# BOTTOM_BRD_v1_0_1.net
KiCad netlist of a schematic drawn in EAGLE
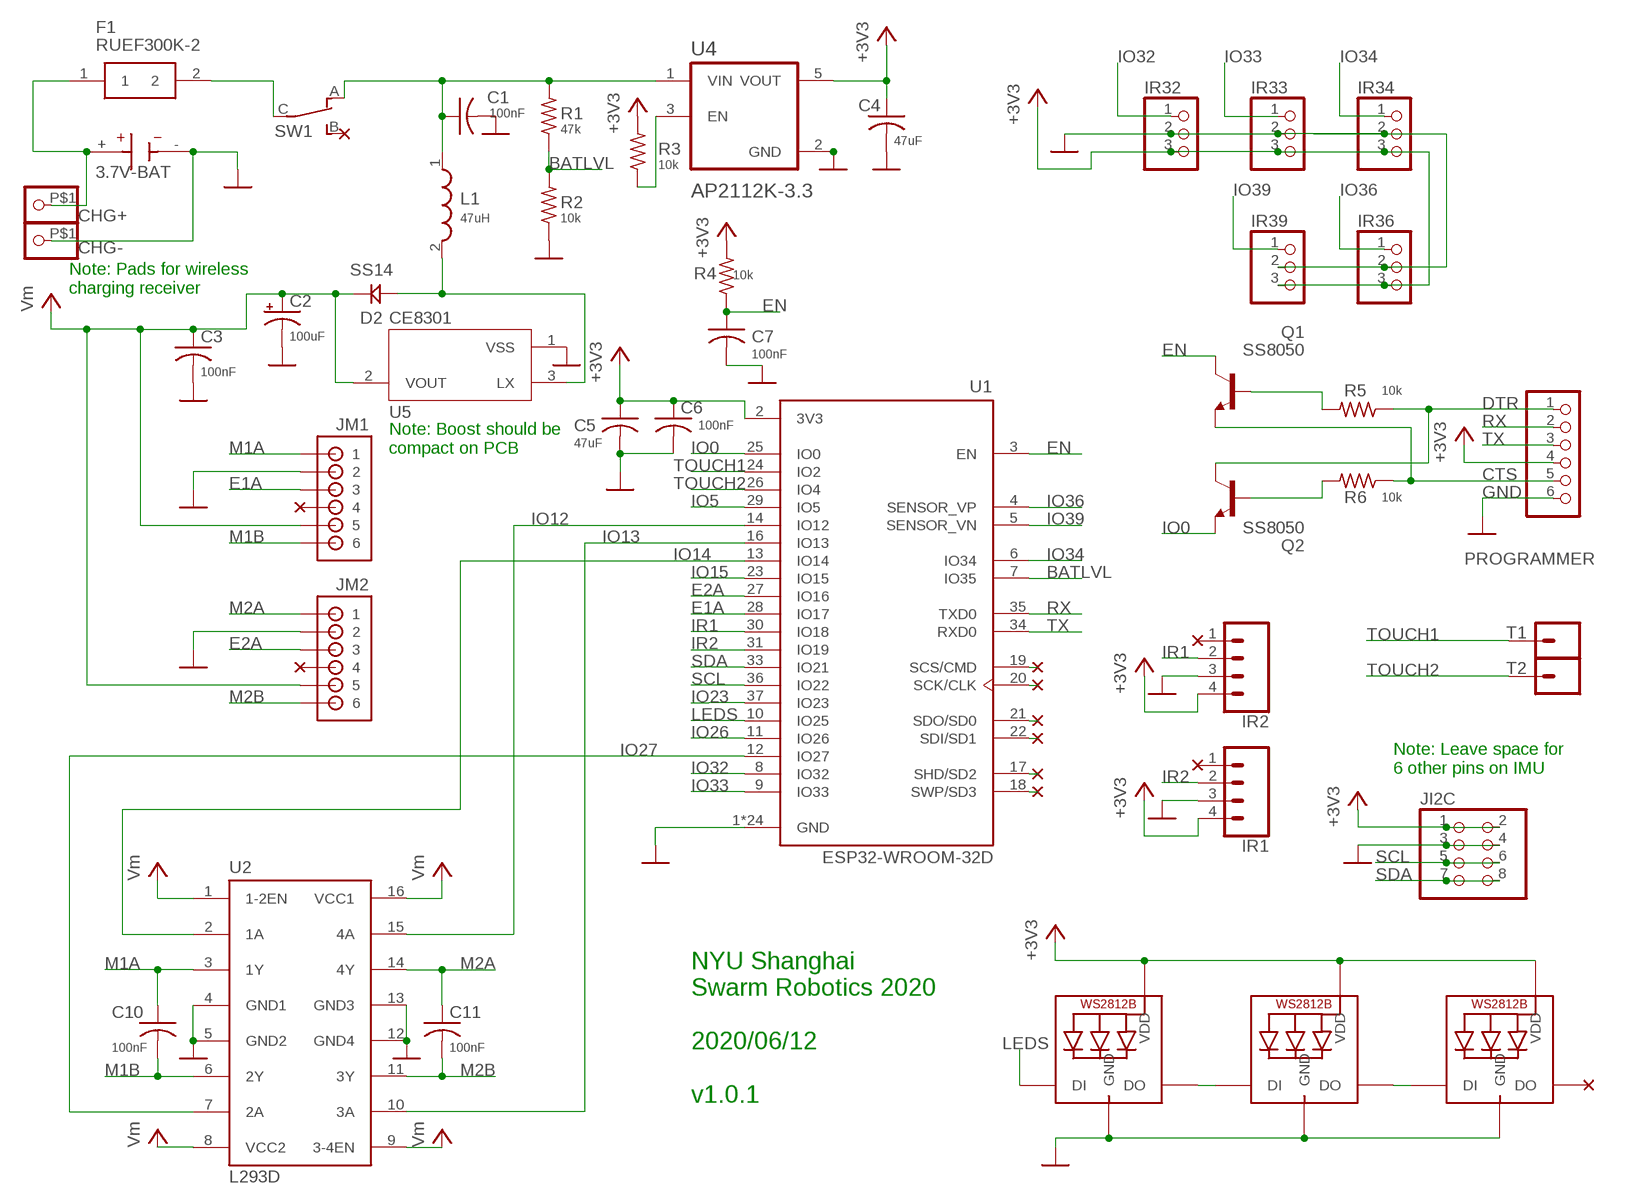
[diagram p0: schematic, sheet 1]

(export (version "E")
  (design (tool "Eeschema 10.0.6"))
  (components
    (comp (ref "BT1")
      (value "3.7V-BAT")
      (footprint "eagle-import:BAT_6S-AA")
      (fields (field (name "MF") "MPD") (field (name "MP") "6S-AA"))
      (libsource (lib "eagle-import") (part "6S-AA"))
    )
    (comp (ref "C1")
      (value "100nF")
      (footprint "eagle-import:C0805")
      (libsource (lib "eagle-import") (part "C-USC0805"))
    )
    (comp (ref "C2")
      (value "100uF")
      (footprint "eagle-import:153CLV-0605")
      (libsource (lib "eagle-import") (part "CPOL-US153CLV-0605"))
    )
    (comp (ref "C3")
      (value "100nF")
      (footprint "eagle-import:C0805")
      (libsource (lib "eagle-import") (part "C-USC0805"))
    )
    (comp (ref "C4")
      (value "47uF")
      (footprint "eagle-import:C0805")
      (libsource (lib "eagle-import") (part "C-USC0805"))
    )
    (comp (ref "C5")
      (value "47uF")
      (footprint "eagle-import:C0805")
      (libsource (lib "eagle-import") (part "C-USC0805"))
    )
    (comp (ref "C6")
      (value "100nF")
      (footprint "eagle-import:C0805")
      (libsource (lib "eagle-import") (part "C-USC0805"))
    )
    (comp (ref "C7")
      (value "100nF")
      (footprint "eagle-import:C0805")
      (libsource (lib "eagle-import") (part "C-USC0805"))
    )
    (comp (ref "C10")
      (value "100nF")
      (footprint "eagle-import:C0805")
      (libsource (lib "eagle-import") (part "C-USC0805"))
    )
    (comp (ref "C11")
      (value "100nF")
      (footprint "eagle-import:C0805")
      (libsource (lib "eagle-import") (part "C-USC0805"))
    )
    (comp (ref "CHARGING")
      (value "WS2812B5050")
      (footprint "eagle-import:WS2812B")
      (libsource (lib "eagle-import") (part "WS2812B5050"))
    )
    (comp (ref "CHG+")
      (value "PINHD-1X1-BIGPOGO")
      (footprint "eagle-import:1X1-BIGPOGO")
      (libsource (lib "eagle-import") (part "PINHD-1X1-BIGPOGO"))
    )
    (comp (ref "CHG-")
      (value "PINHD-1X1-BIGPOGO")
      (footprint "eagle-import:1X1-BIGPOGO")
      (libsource (lib "eagle-import") (part "PINHD-1X1-BIGPOGO"))
    )
    (comp (ref "D2")
      (value "SS14")
      (footprint "eagle-import:DO214")
      (fields (field (name "MF") "ON Semiconductor"))
      (libsource (lib "eagle-import") (part "SS14"))
    )
    (comp (ref "F1")
      (value "RUEF300K-2")
      (footprint "eagle-import:RUEF300K2")
      (libsource (lib "eagle-import") (part "RUEF300K-2"))
    )
    (comp (ref "IR1")
      (value "CONN_04")
      (footprint "eagle-import:1X04")
      (libsource (lib "eagle-import") (part "CONN_04"))
    )
    (comp (ref "IR2")
      (value "CONN_04")
      (footprint "eagle-import:1X04")
      (libsource (lib "eagle-import") (part "CONN_04"))
    )
    (comp (ref "IR32")
      (value "PINHD-1X3")
      (footprint "eagle-import:1X03")
      (libsource (lib "eagle-import") (part "PINHD-1X3"))
    )
    (comp (ref "IR33")
      (value "PINHD-1X3")
      (footprint "eagle-import:1X03")
      (libsource (lib "eagle-import") (part "PINHD-1X3"))
    )
    (comp (ref "IR34")
      (value "PINHD-1X3")
      (footprint "eagle-import:1X03")
      (libsource (lib "eagle-import") (part "PINHD-1X3"))
    )
    (comp (ref "IR36")
      (value "PINHD-1X3")
      (footprint "eagle-import:1X03")
      (libsource (lib "eagle-import") (part "PINHD-1X3"))
    )
    (comp (ref "IR39")
      (value "PINHD-1X3")
      (footprint "eagle-import:1X03")
      (libsource (lib "eagle-import") (part "PINHD-1X3"))
    )
    (comp (ref "JI2C")
      (value "PINHD-2X4")
      (footprint "eagle-import:2X04")
      (libsource (lib "eagle-import") (part "PINHD-2X4"))
    )
    (comp (ref "JM1")
      (value "B6B-ZR")
      (footprint "eagle-import:B6B-ZR")
      (fields (field (name "MF") "JST"))
      (libsource (lib "eagle-import") (part "B6B-ZR"))
    )
    (comp (ref "JM2")
      (value "B6B-ZR")
      (footprint "eagle-import:B6B-ZR")
      (fields (field (name "MF") "JST"))
      (libsource (lib "eagle-import") (part "B6B-ZR"))
    )
    (comp (ref "L1")
      (value "47uH")
      (footprint "eagle-import:INDP5858X480N")
      (fields (field (name "MF") "Bourns") (field (name "MP") "SDR0604-100KL"))
      (libsource (lib "eagle-import") (part "SDR0604-100KL"))
    )
    (comp (ref "POWER")
      (value "WS2812B5050")
      (footprint "eagle-import:WS2812B")
      (libsource (lib "eagle-import") (part "WS2812B5050"))
    )
    (comp (ref "PROGRAMMER")
      (value "PINHD-1X6B")
      (footprint "eagle-import:1X06-BIG")
      (libsource (lib "eagle-import") (part "PINHD-1X6B"))
    )
    (comp (ref "Q1")
      (value "SS8050")
      (footprint "eagle-import:SOT23")
      (libsource (lib "eagle-import") (part "BC850"))
    )
    (comp (ref "Q2")
      (value "SS8050")
      (footprint "eagle-import:SOT23")
      (libsource (lib "eagle-import") (part "BC850"))
    )
    (comp (ref "R1")
      (value "47k")
      (footprint "eagle-import:M0805")
      (libsource (lib "eagle-import") (part "R-US_M0805"))
    )
    (comp (ref "R2")
      (value "10k")
      (footprint "eagle-import:M0805")
      (libsource (lib "eagle-import") (part "R-US_M0805"))
    )
    (comp (ref "R3")
      (value "10k")
      (footprint "eagle-import:M0805")
      (libsource (lib "eagle-import") (part "R-US_M0805"))
    )
    (comp (ref "R4")
      (value "10k")
      (footprint "eagle-import:M0805")
      (libsource (lib "eagle-import") (part "R-US_M0805"))
    )
    (comp (ref "R5")
      (value "10k")
      (footprint "eagle-import:M0805")
      (libsource (lib "eagle-import") (part "R-US_M0805"))
    )
    (comp (ref "R6")
      (value "10k")
      (footprint "eagle-import:M0805")
      (libsource (lib "eagle-import") (part "R-US_M0805"))
    )
    (comp (ref "STATE")
      (value "WS2812B5050")
      (footprint "eagle-import:WS2812B")
      (libsource (lib "eagle-import") (part "WS2812B5050"))
    )
    (comp (ref "SW1")
      (value "CS12ANW03")
      (footprint "eagle-import:CS12ANW03")
      (fields (field (name "MF") "NKK Switches"))
      (libsource (lib "eagle-import") (part "CS12ANW03"))
    )
    (comp (ref "T1")
      (value "CONN_01SPRING-CONN")
      (footprint "eagle-import:SPRING-CONNECTOR")
      (libsource (lib "eagle-import") (part "CONN_01SPRING-CONN"))
    )
    (comp (ref "T2")
      (value "CONN_01SPRING-CONN")
      (footprint "eagle-import:SPRING-CONNECTOR")
      (libsource (lib "eagle-import") (part "CONN_01SPRING-CONN"))
    )
    (comp (ref "U1")
      (value "ESP32-WROOM-32D")
      (footprint "eagle-import:MODULE_ESP32-WROOM-32D")
      (fields (field (name "MF") "Espressif Systems"))
      (libsource (lib "eagle-import") (part "ESP32-WROOM-32D"))
    )
    (comp (ref "U2")
      (value "L293D")
      (footprint "eagle-import:DIL16")
      (libsource (lib "eagle-import") (part "L293D"))
    )
    (comp (ref "U4")
      (value "AP2112K-3.3")
      (footprint "eagle-import:SOT95P285X140-5N")
      (fields (field (name "MF") "Diodes Inc.") (field (name "MP") "AP2112K-3.3TRG1"))
      (libsource (lib "eagle-import") (part "AP2112K-3.3TRG1"))
    )
    (comp (ref "U5")
      (value "CE8301")
      (footprint "eagle-import:REG_MCP1702T-3302E_MB")
      (fields (field (name "MF") "Microchip") (field (name "MP") "MCP1702T-3302E/MB"))
      (libsource (lib "eagle-import") (part "MCP1702T-3302E/MB"))
    )
  )
  (nets
    (net (code "1") (name "+3V3") (class "Default")
      (node (ref "C4") (pin "1") (pinfunction "1_1") (pintype "passive"))
      (node (ref "C5") (pin "1") (pinfunction "1_1") (pintype "passive"))
      (node (ref "C6") (pin "1") (pinfunction "1_1") (pintype "passive"))
      (node (ref "CHARGING") (pin "1-VDD") (pinfunction "VDD_1-VDD") (pintype "power_in"))
      (node (ref "IR1") (pin "4") (pinfunction "4_4") (pintype "passive"))
      (node (ref "IR2") (pin "4") (pinfunction "4_4") (pintype "passive"))
      (node (ref "IR32") (pin "3") (pinfunction "3_3") (pintype "passive"))
      (node (ref "IR33") (pin "3") (pinfunction "3_3") (pintype "passive"))
      (node (ref "IR34") (pin "3") (pinfunction "3_3") (pintype "passive"))
      (node (ref "IR36") (pin "3") (pinfunction "3_3") (pintype "passive"))
      (node (ref "IR39") (pin "3") (pinfunction "3_3") (pintype "passive"))
      (node (ref "JI2C") (pin "1") (pinfunction "1_1") (pintype "passive"))
      (node (ref "JI2C") (pin "2") (pinfunction "2_2") (pintype "passive"))
      (node (ref "POWER") (pin "1-VDD") (pinfunction "VDD_1-VDD") (pintype "power_in"))
      (node (ref "PROGRAMMER") (pin "4") (pinfunction "4_4") (pintype "passive"))
      (node (ref "R3") (pin "2") (pinfunction "2_2") (pintype "passive"))
      (node (ref "R4") (pin "2") (pinfunction "2_2") (pintype "passive"))
      (node (ref "STATE") (pin "1-VDD") (pinfunction "VDD_1-VDD") (pintype "power_in"))
      (node (ref "U1") (pin "2") (pinfunction "3V3_2") (pintype "power_in"))
      (node (ref "U4") (pin "5") (pinfunction "VOUT_5") (pintype "power_in"))
    )
    (net (code "2") (name "/BATLVL") (class "Default")
      (node (ref "R1") (pin "1") (pinfunction "1_1") (pintype "passive"))
      (node (ref "R2") (pin "2") (pinfunction "2_2") (pintype "passive"))
      (node (ref "U1") (pin "7") (pinfunction "IO35_7") (pintype "input"))
    )
    (net (code "3") (name "/CTS") (class "Default")
      (node (ref "PROGRAMMER") (pin "5") (pinfunction "5_5") (pintype "passive"))
      (node (ref "Q1") (pin "2") (pinfunction "E_2") (pintype "passive"))
      (node (ref "R6") (pin "1") (pinfunction "1_1") (pintype "passive"))
    )
    (net (code "4") (name "/DTR") (class "Default")
      (node (ref "PROGRAMMER") (pin "1") (pinfunction "1_1") (pintype "passive"))
      (node (ref "Q2") (pin "3") (pinfunction "C_3") (pintype "passive"))
      (node (ref "R5") (pin "1") (pinfunction "1_1") (pintype "passive"))
    )
    (net (code "5") (name "/E1A") (class "Default")
      (node (ref "JM1") (pin "3") (pinfunction "3_3") (pintype "bidirectional"))
      (node (ref "U1") (pin "28") (pinfunction "IO17_28") (pintype "bidirectional"))
    )
    (net (code "6") (name "/E2A") (class "Default")
      (node (ref "JM2") (pin "3") (pinfunction "3_3") (pintype "bidirectional"))
      (node (ref "U1") (pin "27") (pinfunction "IO16_27") (pintype "bidirectional"))
    )
    (net (code "7") (name "/EN") (class "Default")
      (node (ref "C7") (pin "1") (pinfunction "1_1") (pintype "passive"))
      (node (ref "Q1") (pin "3") (pinfunction "C_3") (pintype "passive"))
      (node (ref "R4") (pin "1") (pinfunction "1_1") (pintype "passive"))
      (node (ref "U1") (pin "3") (pinfunction "EN_3") (pintype "input"))
    )
    (net (code "8") (name "/IO0") (class "Default")
      (node (ref "Q2") (pin "2") (pinfunction "E_2") (pintype "passive"))
      (node (ref "U1") (pin "25") (pinfunction "IO0_25") (pintype "bidirectional"))
    )
    (net (code "9") (name "/IO5") (class "Default")
      (node (ref "U1") (pin "29") (pinfunction "IO5_29") (pintype "bidirectional"))
    )
    (net (code "10") (name "/IO12") (class "Default")
      (node (ref "U1") (pin "14") (pinfunction "IO12_14") (pintype "bidirectional"))
      (node (ref "U2") (pin "15") (pinfunction "4A_15") (pintype "input"))
    )
    (net (code "11") (name "/IO13") (class "Default")
      (node (ref "U1") (pin "16") (pinfunction "IO13_16") (pintype "bidirectional"))
      (node (ref "U2") (pin "10") (pinfunction "3A_10") (pintype "input"))
    )
    (net (code "12") (name "/IO14") (class "Default")
      (node (ref "U1") (pin "13") (pinfunction "IO14_13") (pintype "bidirectional"))
      (node (ref "U2") (pin "2") (pinfunction "1A_2") (pintype "input"))
    )
    (net (code "13") (name "/IO15") (class "Default")
      (node (ref "U1") (pin "23") (pinfunction "IO15_23") (pintype "bidirectional"))
    )
    (net (code "14") (name "/IO23") (class "Default")
      (node (ref "U1") (pin "37") (pinfunction "IO23_37") (pintype "bidirectional"))
    )
    (net (code "15") (name "/IO26") (class "Default")
      (node (ref "U1") (pin "11") (pinfunction "IO26_11") (pintype "bidirectional"))
    )
    (net (code "16") (name "/IO27") (class "Default")
      (node (ref "U1") (pin "12") (pinfunction "IO27_12") (pintype "bidirectional"))
      (node (ref "U2") (pin "7") (pinfunction "2A_7") (pintype "input"))
    )
    (net (code "17") (name "/IO32") (class "Default")
      (node (ref "IR32") (pin "1") (pinfunction "1_1") (pintype "passive"))
      (node (ref "U1") (pin "8") (pinfunction "IO32_8") (pintype "bidirectional"))
    )
    (net (code "18") (name "/IO33") (class "Default")
      (node (ref "IR33") (pin "1") (pinfunction "1_1") (pintype "passive"))
      (node (ref "U1") (pin "9") (pinfunction "IO33_9") (pintype "bidirectional"))
    )
    (net (code "19") (name "/IO34") (class "Default")
      (node (ref "IR34") (pin "1") (pinfunction "1_1") (pintype "passive"))
      (node (ref "U1") (pin "6") (pinfunction "IO34_6") (pintype "input"))
    )
    (net (code "20") (name "/IO36") (class "Default")
      (node (ref "IR36") (pin "1") (pinfunction "1_1") (pintype "passive"))
      (node (ref "U1") (pin "4") (pinfunction "SENSOR_VP_4") (pintype "input"))
    )
    (net (code "21") (name "/IO39") (class "Default")
      (node (ref "IR39") (pin "1") (pinfunction "1_1") (pintype "passive"))
      (node (ref "U1") (pin "5") (pinfunction "SENSOR_VN_5") (pintype "input"))
    )
    (net (code "22") (name "/IR1") (class "Default")
      (node (ref "IR2") (pin "2") (pinfunction "2_2") (pintype "passive"))
      (node (ref "U1") (pin "30") (pinfunction "IO18_30") (pintype "bidirectional"))
    )
    (net (code "23") (name "/IR2") (class "Default")
      (node (ref "IR1") (pin "2") (pinfunction "2_2") (pintype "passive"))
      (node (ref "U1") (pin "31") (pinfunction "IO19_31") (pintype "bidirectional"))
    )
    (net (code "24") (name "/LEDS") (class "Default")
      (node (ref "CHARGING") (pin "4-DIN") (pinfunction "DI_4-DIN") (pintype "input"))
      (node (ref "U1") (pin "10") (pinfunction "IO25_10") (pintype "bidirectional"))
    )
    (net (code "25") (name "/M1A") (class "Default")
      (node (ref "C10") (pin "1") (pinfunction "1_1") (pintype "passive"))
      (node (ref "JM1") (pin "1") (pinfunction "1_1") (pintype "bidirectional"))
      (node (ref "U2") (pin "3") (pinfunction "1Y_3") (pintype "output"))
    )
    (net (code "26") (name "/M1B") (class "Default")
      (node (ref "C10") (pin "2") (pinfunction "2_2") (pintype "passive"))
      (node (ref "JM1") (pin "6") (pinfunction "6_6") (pintype "bidirectional"))
      (node (ref "U2") (pin "6") (pinfunction "2Y_6") (pintype "output"))
    )
    (net (code "27") (name "/M2A") (class "Default")
      (node (ref "C11") (pin "1") (pinfunction "1_1") (pintype "passive"))
      (node (ref "JM2") (pin "1") (pinfunction "1_1") (pintype "bidirectional"))
      (node (ref "U2") (pin "14") (pinfunction "4Y_14") (pintype "output"))
    )
    (net (code "28") (name "/M2B") (class "Default")
      (node (ref "C11") (pin "2") (pinfunction "2_2") (pintype "passive"))
      (node (ref "JM2") (pin "6") (pinfunction "6_6") (pintype "bidirectional"))
      (node (ref "U2") (pin "11") (pinfunction "3Y_11") (pintype "output"))
    )
    (net (code "29") (name "/RX") (class "Default")
      (node (ref "PROGRAMMER") (pin "2") (pinfunction "2_2") (pintype "passive"))
      (node (ref "U1") (pin "35") (pinfunction "TXD0_35") (pintype "bidirectional"))
    )
    (net (code "30") (name "/SCL") (class "Default")
      (node (ref "JI2C") (pin "5") (pinfunction "5_5") (pintype "passive"))
      (node (ref "JI2C") (pin "6") (pinfunction "6_6") (pintype "passive"))
      (node (ref "U1") (pin "36") (pinfunction "IO22_36") (pintype "bidirectional"))
    )
    (net (code "31") (name "/SDA") (class "Default")
      (node (ref "JI2C") (pin "7") (pinfunction "7_7") (pintype "passive"))
      (node (ref "JI2C") (pin "8") (pinfunction "8_8") (pintype "passive"))
      (node (ref "U1") (pin "33") (pinfunction "IO21_33") (pintype "bidirectional"))
    )
    (net (code "32") (name "/TOUCH1") (class "Default")
      (node (ref "T1") (pin "P$2") (pinfunction "1_P$2") (pintype "passive"))
      (node (ref "U1") (pin "24") (pinfunction "IO2_24") (pintype "bidirectional"))
    )
    (net (code "33") (name "/TOUCH2") (class "Default")
      (node (ref "T2") (pin "P$2") (pinfunction "1_P$2") (pintype "passive"))
      (node (ref "U1") (pin "26") (pinfunction "IO4_26") (pintype "bidirectional"))
    )
    (net (code "34") (name "/TX") (class "Default")
      (node (ref "PROGRAMMER") (pin "3") (pinfunction "3_3") (pintype "passive"))
      (node (ref "U1") (pin "34") (pinfunction "RXD0_34") (pintype "bidirectional"))
    )
    (net (code "35") (name "GND") (class "Default")
      (node (ref "BT1") (pin "-") (pinfunction "-_-") (pintype "passive"))
      (node (ref "C1") (pin "2") (pinfunction "2_2") (pintype "passive"))
      (node (ref "C2") (pin "-") (pinfunction "-_-") (pintype "passive"))
      (node (ref "C3") (pin "2") (pinfunction "2_2") (pintype "passive"))
      (node (ref "C4") (pin "2") (pinfunction "2_2") (pintype "passive"))
      (node (ref "C5") (pin "2") (pinfunction "2_2") (pintype "passive"))
      (node (ref "C6") (pin "2") (pinfunction "2_2") (pintype "passive"))
      (node (ref "C7") (pin "2") (pinfunction "2_2") (pintype "passive"))
      (node (ref "CHARGING") (pin "3-GND") (pinfunction "GND_3-GND") (pintype "power_in"))
      (node (ref "CHG-") (pin "P$1") (pinfunction "1_P$1") (pintype "passive"))
      (node (ref "IR1") (pin "3") (pinfunction "3_3") (pintype "passive"))
      (node (ref "IR2") (pin "3") (pinfunction "3_3") (pintype "passive"))
      (node (ref "IR32") (pin "2") (pinfunction "2_2") (pintype "passive"))
      (node (ref "IR33") (pin "2") (pinfunction "2_2") (pintype "passive"))
      (node (ref "IR34") (pin "2") (pinfunction "2_2") (pintype "passive"))
      (node (ref "IR36") (pin "2") (pinfunction "2_2") (pintype "passive"))
      (node (ref "IR39") (pin "2") (pinfunction "2_2") (pintype "passive"))
      (node (ref "JI2C") (pin "3") (pinfunction "3_3") (pintype "passive"))
      (node (ref "JI2C") (pin "4") (pinfunction "4_4") (pintype "passive"))
      (node (ref "JM1") (pin "2") (pinfunction "2_2") (pintype "bidirectional"))
      (node (ref "JM2") (pin "2") (pinfunction "2_2") (pintype "bidirectional"))
      (node (ref "POWER") (pin "3-GND") (pinfunction "GND_3-GND") (pintype "power_in"))
      (node (ref "PROGRAMMER") (pin "6") (pinfunction "6_6") (pintype "passive"))
      (node (ref "R2") (pin "1") (pinfunction "1_1") (pintype "passive"))
      (node (ref "STATE") (pin "3-GND") (pinfunction "GND_3-GND") (pintype "power_in"))
      (node (ref "U1") (pin "1") (pinfunction "GND_1") (pintype "power_in"))
      (node (ref "U1") (pin "15") (pinfunction "GND_15") (pintype "power_in"))
      (node (ref "U1") (pin "38") (pinfunction "GND_38") (pintype "power_in"))
      (node (ref "U1") (pin "39_1") (pinfunction "GND_39_1") (pintype "power_in"))
      (node (ref "U1") (pin "39_10") (pinfunction "GND_39_10") (pintype "power_in"))
      (node (ref "U1") (pin "39_11") (pinfunction "GND_39_11") (pintype "power_in"))
      (node (ref "U1") (pin "39_12") (pinfunction "GND_39_12") (pintype "power_in"))
      (node (ref "U1") (pin "39_13") (pinfunction "GND_39_13") (pintype "power_in"))
      (node (ref "U1") (pin "39_14") (pinfunction "GND_39_14") (pintype "power_in"))
      (node (ref "U1") (pin "39_15") (pinfunction "GND_39_15") (pintype "power_in"))
      (node (ref "U1") (pin "39_16") (pinfunction "GND_39_16") (pintype "power_in"))
      (node (ref "U1") (pin "39_17") (pinfunction "GND_39_17") (pintype "power_in"))
      (node (ref "U1") (pin "39_18") (pinfunction "GND_39_18") (pintype "power_in"))
      (node (ref "U1") (pin "39_19") (pinfunction "GND_39_19") (pintype "power_in"))
      (node (ref "U1") (pin "39_2") (pinfunction "GND_39_2") (pintype "power_in"))
      (node (ref "U1") (pin "39_20") (pinfunction "GND_39_20") (pintype "power_in"))
      (node (ref "U1") (pin "39_21") (pinfunction "GND_39_21") (pintype "power_in"))
      (node (ref "U1") (pin "39_3") (pinfunction "GND_39_3") (pintype "power_in"))
      (node (ref "U1") (pin "39_4") (pinfunction "GND_39_4") (pintype "power_in"))
      (node (ref "U1") (pin "39_5") (pinfunction "GND_39_5") (pintype "power_in"))
      (node (ref "U1") (pin "39_6") (pinfunction "GND_39_6") (pintype "power_in"))
      (node (ref "U1") (pin "39_7") (pinfunction "GND_39_7") (pintype "power_in"))
      (node (ref "U1") (pin "39_8") (pinfunction "GND_39_8") (pintype "power_in"))
      (node (ref "U1") (pin "39_9") (pinfunction "GND_39_9") (pintype "power_in"))
      (node (ref "U2") (pin "12") (pinfunction "GND4_12") (pintype "power_in"))
      (node (ref "U2") (pin "13") (pinfunction "GND3_13") (pintype "power_in"))
      (node (ref "U2") (pin "4") (pinfunction "GND1_4") (pintype "power_in"))
      (node (ref "U2") (pin "5") (pinfunction "GND2_5") (pintype "power_in"))
      (node (ref "U4") (pin "2") (pinfunction "GND_2") (pintype "power_in"))
      (node (ref "U5") (pin "1") (pinfunction "VSS_1") (pintype "power_in"))
    )
    (net (code "36") (name "Net-(CHARGING-DO)") (class "Default")
      (node (ref "CHARGING") (pin "2-DOUT") (pinfunction "DO_2-DOUT") (pintype "output"))
      (node (ref "POWER") (pin "4-DIN") (pinfunction "DI_4-DIN") (pintype "input"))
    )
    (net (code "37") (name "Net-(CHG+-1)") (class "Default")
      (node (ref "BT1") (pin "+") (pinfunction "+_+") (pintype "passive"))
      (node (ref "CHG+") (pin "P$1") (pinfunction "1_P$1") (pintype "passive"))
      (node (ref "F1") (pin "1") (pinfunction "1_1") (pintype "bidirectional"))
    )
    (net (code "38") (name "Net-(F1-Pad2)") (class "Default")
      (node (ref "F1") (pin "2") (pinfunction "2_2") (pintype "bidirectional"))
      (node (ref "SW1") (pin "C") (pinfunction "C_C") (pintype "passive"))
    )
    (net (code "39") (name "Net-(POWER-DO)") (class "Default")
      (node (ref "POWER") (pin "2-DOUT") (pinfunction "DO_2-DOUT") (pintype "output"))
      (node (ref "STATE") (pin "4-DIN") (pinfunction "DI_4-DIN") (pintype "input"))
    )
    (net (code "40") (name "Net-(Q1-B)") (class "Default")
      (node (ref "Q1") (pin "1") (pinfunction "B_1") (pintype "passive"))
      (node (ref "R5") (pin "2") (pinfunction "2_2") (pintype "passive"))
    )
    (net (code "41") (name "Net-(Q2-B)") (class "Default")
      (node (ref "Q2") (pin "1") (pinfunction "B_1") (pintype "passive"))
      (node (ref "R6") (pin "2") (pinfunction "2_2") (pintype "passive"))
    )
    (net (code "42") (name "Net-(U4-EN)") (class "Default")
      (node (ref "R3") (pin "1") (pinfunction "1_1") (pintype "passive"))
      (node (ref "U4") (pin "3") (pinfunction "EN_3") (pintype "input"))
    )
    (net (code "43") (name "Net-(U4-VIN)") (class "Default")
      (node (ref "C1") (pin "1") (pinfunction "1_1") (pintype "passive"))
      (node (ref "L1") (pin "1") (pinfunction "1_1") (pintype "passive"))
      (node (ref "R1") (pin "2") (pinfunction "2_2") (pintype "passive"))
      (node (ref "SW1") (pin "A") (pinfunction "A_A") (pintype "passive"))
      (node (ref "U4") (pin "1") (pinfunction "VIN_1") (pintype "power_in"))
    )
    (net (code "44") (name "Net-(U5-LX)") (class "Default")
      (node (ref "D2") (pin "ANODE") (pinfunction "ANODE_ANODE") (pintype "bidirectional"))
      (node (ref "L1") (pin "2") (pinfunction "2_2") (pintype "passive"))
      (node (ref "U5") (pin "3") (pinfunction "LX_3") (pintype "output"))
    )
    (net (code "45") (name "Vm") (class "Default")
      (node (ref "C2") (pin "+") (pinfunction "+_+") (pintype "passive"))
      (node (ref "C3") (pin "1") (pinfunction "1_1") (pintype "passive"))
      (node (ref "D2") (pin "CATHODE") (pinfunction "KATHODE_CATHODE") (pintype "bidirectional"))
      (node (ref "JM1") (pin "5") (pinfunction "5_5") (pintype "bidirectional"))
      (node (ref "JM2") (pin "5") (pinfunction "5_5") (pintype "bidirectional"))
      (node (ref "U2") (pin "1") (pinfunction "1-2EN_1") (pintype "input"))
      (node (ref "U2") (pin "16") (pinfunction "VCC1_16") (pintype "power_in"))
      (node (ref "U2") (pin "8") (pinfunction "VCC2_8") (pintype "power_in"))
      (node (ref "U2") (pin "9") (pinfunction "3-4EN_9") (pintype "input"))
      (node (ref "U5") (pin "2") (pinfunction "VOUT_2") (pintype "input"))
    )
    (net (code "46") (name "unconnected-(IR1-Pad1)") (class "Default")
      (node (ref "IR1") (pin "1") (pinfunction "1_1") (pintype "passive"))
    )
    (net (code "47") (name "unconnected-(IR2-Pad1)") (class "Default")
      (node (ref "IR2") (pin "1") (pinfunction "1_1") (pintype "passive"))
    )
    (net (code "48") (name "unconnected-(JM1-Pad4)") (class "Default")
      (node (ref "JM1") (pin "4") (pinfunction "4_4") (pintype "bidirectional"))
    )
    (net (code "49") (name "unconnected-(JM2-Pad4)") (class "Default")
      (node (ref "JM2") (pin "4") (pinfunction "4_4") (pintype "bidirectional"))
    )
    (net (code "50") (name "unconnected-(STATE-DO-Pad2-DOUT)") (class "Default")
      (node (ref "STATE") (pin "2-DOUT") (pinfunction "DO_2-DOUT") (pintype "output"))
    )
    (net (code "51") (name "unconnected-(SW1-PadB)") (class "Default")
      (node (ref "SW1") (pin "B") (pinfunction "B_B") (pintype "passive"))
    )
    (net (code "52") (name "unconnected-(U1-SCK{slash}CLK-Pad20)") (class "Default")
      (node (ref "U1") (pin "20") (pinfunction "SCK/CLK_20") (pintype "bidirectional"))
    )
    (net (code "53") (name "unconnected-(U1-SCS{slash}CMD-Pad19)") (class "Default")
      (node (ref "U1") (pin "19") (pinfunction "SCS/CMD_19") (pintype "bidirectional"))
    )
    (net (code "54") (name "unconnected-(U1-SDI{slash}SD1-Pad22)") (class "Default")
      (node (ref "U1") (pin "22") (pinfunction "SDI/SD1_22") (pintype "bidirectional"))
    )
    (net (code "55") (name "unconnected-(U1-SDO{slash}SD0-Pad21)") (class "Default")
      (node (ref "U1") (pin "21") (pinfunction "SDO/SD0_21") (pintype "bidirectional"))
    )
    (net (code "56") (name "unconnected-(U1-SHD{slash}SD2-Pad17)") (class "Default")
      (node (ref "U1") (pin "17") (pinfunction "SHD/SD2_17") (pintype "bidirectional"))
    )
    (net (code "57") (name "unconnected-(U1-SWP{slash}SD3-Pad18)") (class "Default")
      (node (ref "U1") (pin "18") (pinfunction "SWP/SD3_18") (pintype "bidirectional"))
    )
  )
)
